# GNSS_GPS.net
KiCad netlist of a schematic drawn in Altium Designer
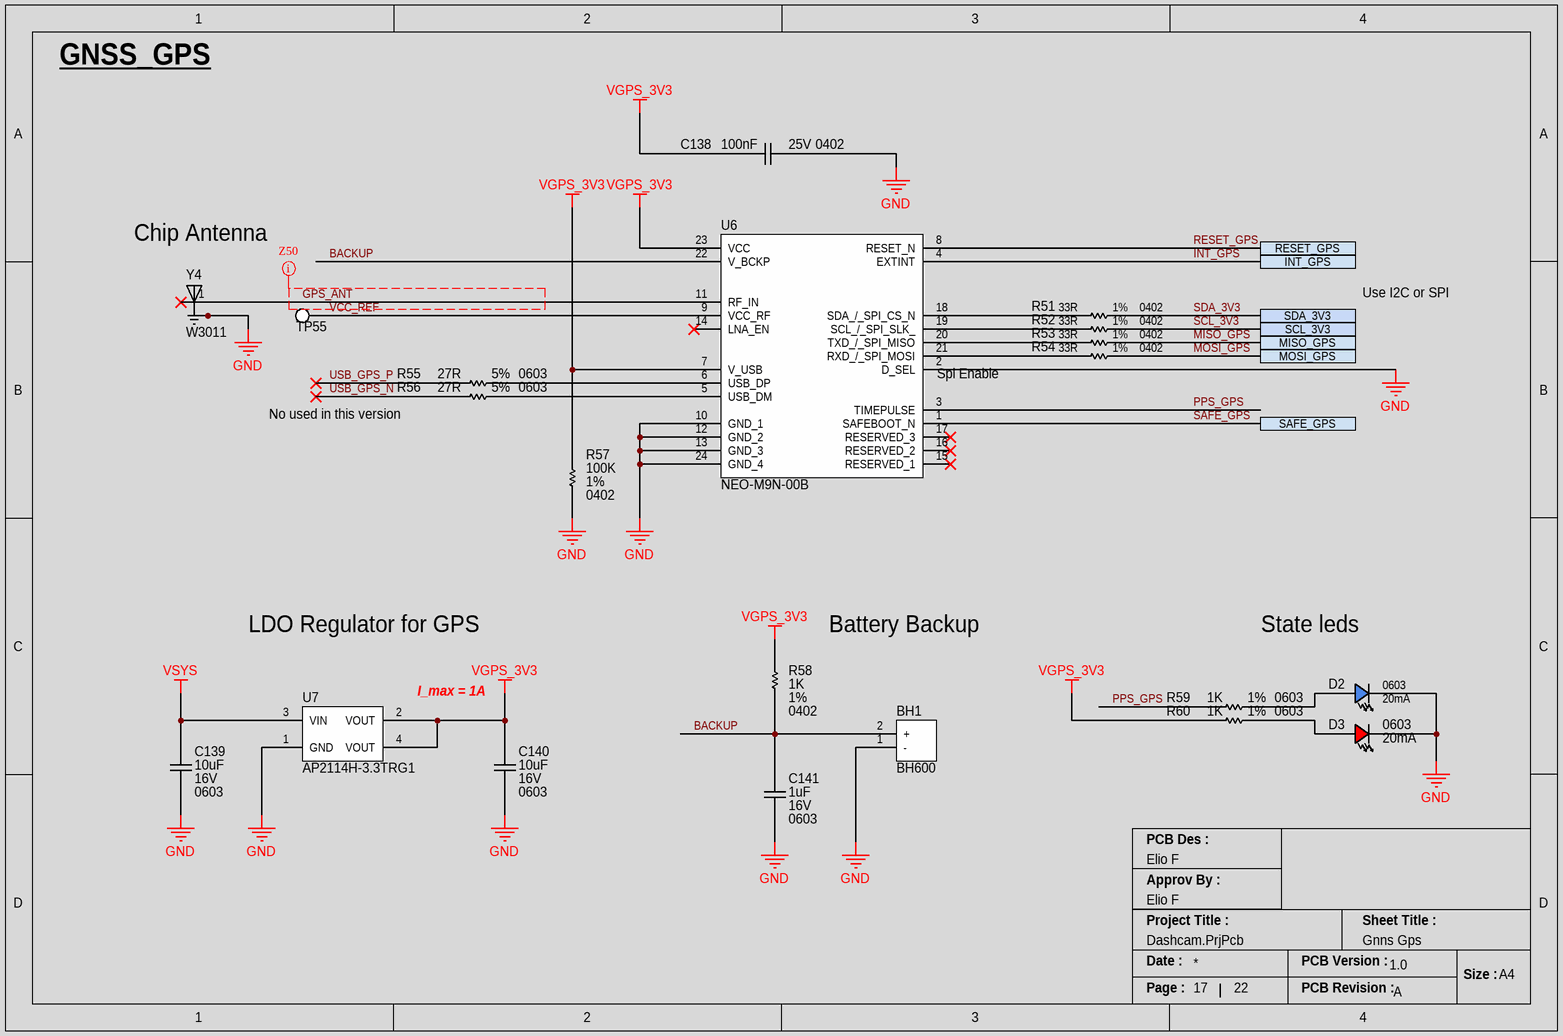
[diagram p0: GNSS_GPS.SchDoc]

(export (version "E")
  (design (tool "Eeschema 10.0.6"))
  (components
    (comp (ref "BH1")
      (value "BH600")
      (footprint "MECH_BATTERY_HOLDER_BH600")
      (description "Battery Holder 1 Cells Thermoplastic Tray")
      (fields (field (name "MANUFACTURER") "Memory Protection Devices"))
      (libsource (lib "Electronic Devices_LIB") (part "MECH_BATTERY_HOLDER_BH600"))
    )
    (comp (ref "C138")
      (value "CC0402KRX5R8BB104")
      (footprint "CAP_0402_CAPC1005X05N")
      (description "Multilayer Ceramic Capacitor, 0.1 uF, 25 V, ± 10%, X7R, 0402 [1005 Metric]")
      (fields
        (field (name "MANUFACTURER") "Yageo")
        (field (name "TOLERANCE") "10%")
        (field (name "CAPACITANCE") "100nF")
        (field (name "VOLTAGE RATING") "25V")
        (field (name "CASE/PACKAGE") "0402")
      )
      (libsource (lib "Electronic Devices_LIB") (part "CAP_100NF_25V_X7R_0402"))
    )
    (comp (ref "C139")
      (value "GRM188R61C106MAALD")
      (footprint "CAP_0603_CAPC1608X08N")
      (description "0603 10 uF 16 V ±20% Tolerance X5R Multilayer Ceramic Chip Capacitor")
      (fields
        (field (name "MANUFACTURER") "Murata")
        (field (name "TOLERANCE") "20%")
        (field (name "VOLTAGE RATING") "16V")
        (field (name "CAPACITANCE") "10uF")
        (field (name "CASE/PACKAGE") "0603")
      )
      (libsource (lib "Electronic Devices_LIB") (part "CAP_10UF_16V_X5R_0603"))
    )
    (comp (ref "C140")
      (value "GRM188R61C106MAALD")
      (footprint "CAP_0603_CAPC1608X08N")
      (description "0603 10 uF 16 V ±20% Tolerance X5R Multilayer Ceramic Chip Capacitor")
      (fields
        (field (name "MANUFACTURER") "Murata")
        (field (name "TOLERANCE") "20%")
        (field (name "VOLTAGE RATING") "16V")
        (field (name "CAPACITANCE") "10uF")
        (field (name "CASE/PACKAGE") "0603")
      )
      (libsource (lib "Electronic Devices_LIB") (part "CAP_10UF_16V_X5R_0603"))
    )
    (comp (ref "C141")
      (value "CL10A105KO8NNNC")
      (footprint "CAP_0603_CAPC1608X08N")
      (description "CAP CER 1UF 16V X5R 0603")
      (fields
        (field (name "MANUFACTURER") "Samsung")
        (field (name "TOLERANCE") "10%")
        (field (name "VOLTAGE RATING") "16V")
        (field (name "CAPACITANCE") "1uF")
        (field (name "CASE/PACKAGE") "0603")
      )
      (libsource (lib "Electronic Devices_LIB") (part "CAP_1UF_16V_X5R_0603"))
    )
    (comp (ref "D2")
      (value "ASCKCB00-NS3T4010302")
      (footprint "LED_0603-BLUE-0.75mm")
      (description "LED Single Chip Blue 467nm 20mA 2-Pin DFN T/R")
      (fields
        (field (name "MANUFACTURER") "Broadcom")
        (field (name "CASE/PACKCAGE") "0603")
        (field (name "TEST CURRENT") "20mA")
      )
      (libsource (lib "Electronic Devices_LIB") (part "LED_DIO_BLUE_20mA_0603_ASCKCB00-NS3T4010302"))
    )
    (comp (ref "D3")
      (value "LTST-C190KRKT")
      (footprint "LED_0603-RED-0.75mm")
      (description "LED,  LTST-C190KRKT")
      (fields
        (field (name "MANUFACTURER") "Vishay Lite-On")
        (field (name "TEST CURRENT") "20mA")
        (field (name "CASE/PACKAGE") "0603")
      )
      (libsource (lib "Electronic Devices_LIB") (part "LED_DIO_RED_20mA_0603"))
    )
    (comp (ref "R51")
      (value "RC0402FR-0733RL")
      (footprint "RES_0402_RESC1005X04N")
      (description "SMD Chip Resistor, 33 Ohm, ± 1%, 62.5 mW, 0402 [1005 Metric], Thick Film, General Purpose")
      (fields
        (field (name "MANUFACTURER") "Yageo")
        (field (name "TOLERANCE") "1%")
        (field (name "RESISTANCE") "33R")
        (field (name "CASE/PACKAGE") "0402")
      )
      (libsource (lib "Electronic Devices_LIB") (part "RES_33R_1%_62.5mW_0402"))
    )
    (comp (ref "R52")
      (value "RC0402FR-0733RL")
      (footprint "RES_0402_RESC1005X04N")
      (description "SMD Chip Resistor, 33 Ohm, ± 1%, 62.5 mW, 0402 [1005 Metric], Thick Film, General Purpose")
      (fields
        (field (name "MANUFACTURER") "Yageo")
        (field (name "TOLERANCE") "1%")
        (field (name "RESISTANCE") "33R")
        (field (name "CASE/PACKAGE") "0402")
      )
      (libsource (lib "Electronic Devices_LIB") (part "RES_33R_1%_62.5mW_0402"))
    )
    (comp (ref "R53")
      (value "RC0402FR-0733RL")
      (footprint "RES_0402_RESC1005X04N")
      (description "SMD Chip Resistor, 33 Ohm, ± 1%, 62.5 mW, 0402 [1005 Metric], Thick Film, General Purpose")
      (fields
        (field (name "MANUFACTURER") "Yageo")
        (field (name "TOLERANCE") "1%")
        (field (name "RESISTANCE") "33R")
        (field (name "CASE/PACKAGE") "0402")
      )
      (libsource (lib "Electronic Devices_LIB") (part "RES_33R_1%_62.5mW_0402"))
    )
    (comp (ref "R54")
      (value "RC0402FR-0733RL")
      (footprint "RES_0402_RESC1005X04N")
      (description "SMD Chip Resistor, 33 Ohm, ± 1%, 62.5 mW, 0402 [1005 Metric], Thick Film, General Purpose")
      (fields
        (field (name "MANUFACTURER") "Yageo")
        (field (name "TOLERANCE") "1%")
        (field (name "RESISTANCE") "33R")
        (field (name "CASE/PACKAGE") "0402")
      )
      (libsource (lib "Electronic Devices_LIB") (part "RES_33R_1%_62.5mW_0402"))
    )
    (comp (ref "R55")
      (value "RC0603JR-0727RL")
      (footprint "RES_0603_RESC1608X04N")
      (description "Res Thick Film 0603 27 Ohm 5% 0.1W(1/10W) ±100ppm/C Pad SMD T/R")
      (fields
        (field (name "MANUFACTURER") "Yageo")
        (field (name "TOLERANCE") "5%")
        (field (name "RESISTANCE") "27R")
        (field (name "CASE/PACKAGE") "0603")
      )
      (libsource (lib "Electronic Devices_LIB") (part "RES_27R_5%_100mW_0603"))
    )
    (comp (ref "R56")
      (value "RC0603JR-0727RL")
      (footprint "RES_0603_RESC1608X04N")
      (description "Res Thick Film 0603 27 Ohm 5% 0.1W(1/10W) ±100ppm/C Pad SMD T/R")
      (fields
        (field (name "MANUFACTURER") "Yageo")
        (field (name "TOLERANCE") "5%")
        (field (name "RESISTANCE") "27R")
        (field (name "CASE/PACKAGE") "0603")
      )
      (libsource (lib "Electronic Devices_LIB") (part "RES_27R_5%_100mW_0603"))
    )
    (comp (ref "R57")
      (value "RC0402FR-07100KL")
      (footprint "RES_0402_RESC1005X04N")
      (description "SMD Chip Resistor, 100 kOhm, ± 1%, 63 mW, 0402 [1005 Metric], Thick Film, General Purpose")
      (fields
        (field (name "MANUFACTURER") "Yageo")
        (field (name "RESISTANCE") "100K")
        (field (name "TOLERANCE") "1%")
        (field (name "CASE/PACKAGE") "0402")
      )
      (libsource (lib "Electronic Devices_LIB") (part "RES_100K_1%_100mW_0402"))
    )
    (comp (ref "R58")
      (value "ERJ-2RKF1001X")
      (footprint "RES_0402_RESC1005X04N")
      (description "RES SMD 1K OHM 1% 1/10W 0402")
      (fields
        (field (name "MANUFACTURER") "Panasonic")
        (field (name "RESISTANCE") "1K")
        (field (name "TOLERANCE") "1%")
        (field (name "CASE/PACKAGE") "0402")
      )
      (libsource (lib "Electronic Devices_LIB") (part "RES_1K_1%_100mW_0402"))
    )
    (comp (ref "R59")
      (value "AC0603FR-101KL")
      (footprint "RES_0603_RESC1608X04N")
      (description "Chip Resistor Automotive Grade Thick Film 0603 1kOhm 1% Paper T/R")
      (fields
        (field (name "MANUFACTURER") "Yageo")
        (field (name "RESISTANCE") "1K")
        (field (name "TOLERANCE") "1%")
        (field (name "CASE/PACKAGE") "0603")
      )
      (libsource (lib "Electronic Devices_LIB") (part "RES_1K_1%_100mW_0603"))
    )
    (comp (ref "R60")
      (value "AC0603FR-101KL")
      (footprint "RES_0603_RESC1608X04N")
      (description "Chip Resistor Automotive Grade Thick Film 0603 1kOhm 1% Paper T/R")
      (fields
        (field (name "MANUFACTURER") "Yageo")
        (field (name "RESISTANCE") "1K")
        (field (name "TOLERANCE") "1%")
        (field (name "CASE/PACKAGE") "0603")
      )
      (libsource (lib "Electronic Devices_LIB") (part "RES_1K_1%_100mW_0603"))
    )
    (comp (ref "TP55")
      (value "NO COMPONENT")
      (footprint "TP_PAD_1.6MM_SMD_ROUND")
      (description "Test Point, SMD pad, round, 1.5mm, 1.6mm, 3mm diameter")
      (libsource (lib "Electronic Devices_LIB") (part "TP_PAD_SMD_Round"))
    )
    (comp (ref "U6")
      (value "NEO-M9N-00B")
      (footprint "IC_MODULE_UBLOX_NEOM9N00B")
      (description "GNSS module, Flash, TCXO, SAW, LNA, LCC, 12x16 mm Professional Grade")
      (fields (field (name "MANUFACTURER") "u-blox"))
      (libsource (lib "Electronic Devices_LIB") (part "IC_MODULE_UBLOX_NEO-M9N-00B"))
    )
    (comp (ref "U7")
      (value "AP2114H-3.3TRG1")
      (footprint "IC_REG_SOT230P700X180-4N")
      (description "IC REG LDO 3.3V 1A SOT223")
      (fields (field (name "MANUFACTURER") "Diodes"))
      (libsource (lib "Electronic Devices_LIB") (part "IC_REG_LDO_3.3V_1A_AP2114H-3.3TRG1"))
    )
    (comp (ref "Y4")
      (value "W3011")
      (footprint "ANTENNA_CHIP_XDCR_W3011")
      (description "Antenna Ceramic 3.4dB Gain 1585.42MHz 2-Pin CSMD")
      (fields (field (name "MANUFACTURER") "Pulse"))
      (libsource (lib "Electronic Devices_LIB") (part "ANT_CHIP_GPS_W3011"))
    )
  )
  (nets
    (net (code "1") (name "/BACKUP") (class "Default")
      (node (ref "BH1") (pin "2") (pinfunction "+_2") (pintype "passive"))
      (node (ref "C141") (pin "2") (pinfunction "2_2") (pintype "passive"))
      (node (ref "R58") (pin "1") (pinfunction "1_1") (pintype "passive"))
      (node (ref "U6") (pin "22") (pinfunction "V_BCKP_22") (pintype "passive"))
    )
    (net (code "2") (name "/GPS_ANT") (class "Default")
      (node (ref "U6") (pin "11") (pinfunction "RF_IN_11") (pintype "passive"))
      (node (ref "Y4") (pin "1") (pinfunction "FEED_1") (pintype "passive"))
    )
    (net (code "3") (name "/INT_GPS") (class "Default")
      (node (ref "U6") (pin "4") (pinfunction "EXTINT_4") (pintype "passive"))
    )
    (net (code "4") (name "/MISO_GPS") (class "Default")
      (node (ref "R53") (pin "2") (pinfunction "2_2") (pintype "passive"))
    )
    (net (code "5") (name "/MOSI_GPS") (class "Default")
      (node (ref "R54") (pin "2") (pinfunction "2_2") (pintype "passive"))
    )
    (net (code "6") (name "/PPS_GPS") (class "Default")
      (node (ref "R59") (pin "1") (pinfunction "1_1") (pintype "passive"))
      (node (ref "U6") (pin "3") (pinfunction "TIMEPULSE_3") (pintype "passive"))
    )
    (net (code "7") (name "/RESET_GPS") (class "Default")
      (node (ref "U6") (pin "8") (pinfunction "RESET_N_8") (pintype "passive"))
    )
    (net (code "8") (name "/SAFE_GPS") (class "Default")
      (node (ref "U6") (pin "1") (pinfunction "SAFEBOOT_N_1") (pintype "passive"))
    )
    (net (code "9") (name "/SCL_3V3") (class "Default")
      (node (ref "R52") (pin "2") (pinfunction "2_2") (pintype "passive"))
    )
    (net (code "10") (name "/SDA_3V3") (class "Default")
      (node (ref "R51") (pin "2") (pinfunction "2_2") (pintype "passive"))
    )
    (net (code "11") (name "/USB_GPS_N") (class "Default")
      (node (ref "R56") (pin "1") (pinfunction "1_1") (pintype "passive+no_connect"))
    )
    (net (code "12") (name "/USB_GPS_P") (class "Default")
      (node (ref "R55") (pin "1") (pinfunction "1_1") (pintype "passive+no_connect"))
    )
    (net (code "13") (name "/VCC_REF") (class "Default")
      (node (ref "TP55") (pin "1") (pinfunction "1_1") (pintype "passive"))
      (node (ref "U6") (pin "9") (pinfunction "VCC_RF_9") (pintype "passive"))
    )
    (net (code "14") (name "GND") (class "Default")
      (node (ref "BH1") (pin "1") (pinfunction "-_1") (pintype "passive"))
      (node (ref "C138") (pin "2") (pinfunction "2_2") (pintype "passive"))
      (node (ref "C139") (pin "1") (pinfunction "1_1") (pintype "passive"))
      (node (ref "C140") (pin "1") (pinfunction "1_1") (pintype "passive"))
      (node (ref "C141") (pin "1") (pinfunction "1_1") (pintype "passive"))
      (node (ref "D2") (pin "1") (pinfunction "C_1") (pintype "passive"))
      (node (ref "D3") (pin "1") (pinfunction "C_1") (pintype "passive"))
      (node (ref "R57") (pin "1") (pinfunction "1_1") (pintype "passive"))
      (node (ref "U6") (pin "10") (pinfunction "GND_1_10") (pintype "passive"))
      (node (ref "U6") (pin "12") (pinfunction "GND_2_12") (pintype "passive"))
      (node (ref "U6") (pin "13") (pinfunction "GND_3_13") (pintype "passive"))
      (node (ref "U6") (pin "2") (pinfunction "D_SEL_2") (pintype "passive"))
      (node (ref "U6") (pin "24") (pinfunction "GND_4_24") (pintype "passive"))
      (node (ref "U7") (pin "1") (pinfunction "GND_1") (pintype "passive"))
      (node (ref "Y4") (pin "2") (pinfunction "GND_2") (pintype "power_in"))
      (node (ref "Y4") (pin "3") (pinfunction "GND_3") (pintype "passive"))
    )
    (net (code "15") (name "Net-(D2-A)") (class "Default")
      (node (ref "D2") (pin "2") (pinfunction "A_2") (pintype "passive"))
      (node (ref "R59") (pin "2") (pinfunction "2_2") (pintype "passive"))
    )
    (net (code "16") (name "Net-(D3-A)") (class "Default")
      (node (ref "D3") (pin "2") (pinfunction "A_2") (pintype "passive"))
      (node (ref "R60") (pin "2") (pinfunction "2_2") (pintype "passive"))
    )
    (net (code "17") (name "Net-(U6-RXD_{slash}_SPI_MOSI)") (class "Default")
      (node (ref "R54") (pin "1") (pinfunction "1_1") (pintype "passive"))
      (node (ref "U6") (pin "21") (pinfunction "RXD_/_SPI_MOSI_21") (pintype "passive"))
    )
    (net (code "18") (name "Net-(U6-SCL_{slash}_SPI_SLK_)") (class "Default")
      (node (ref "R52") (pin "1") (pinfunction "1_1") (pintype "passive"))
      (node (ref "U6") (pin "19") (pinfunction "SCL_/_SPI_SLK__19") (pintype "passive"))
    )
    (net (code "19") (name "Net-(U6-SDA_{slash}_SPI_CS_N)") (class "Default")
      (node (ref "R51") (pin "1") (pinfunction "1_1") (pintype "passive"))
      (node (ref "U6") (pin "18") (pinfunction "SDA_/_SPI_CS_N_18") (pintype "passive"))
    )
    (net (code "20") (name "Net-(U6-TXD_{slash}_SPI_MISO)") (class "Default")
      (node (ref "R53") (pin "1") (pinfunction "1_1") (pintype "passive"))
      (node (ref "U6") (pin "20") (pinfunction "TXD_/_SPI_MISO_20") (pintype "passive"))
    )
    (net (code "21") (name "Net-(U6-USB_DM)") (class "Default")
      (node (ref "R56") (pin "2") (pinfunction "2_2") (pintype "passive"))
      (node (ref "U6") (pin "5") (pinfunction "USB_DM_5") (pintype "passive"))
    )
    (net (code "22") (name "Net-(U6-USB_DP)") (class "Default")
      (node (ref "R55") (pin "2") (pinfunction "2_2") (pintype "passive"))
      (node (ref "U6") (pin "6") (pinfunction "USB_DP_6") (pintype "passive"))
    )
    (net (code "23") (name "VGPS_3V3") (class "Default")
      (node (ref "C138") (pin "1") (pinfunction "1_1") (pintype "passive"))
      (node (ref "C140") (pin "2") (pinfunction "2_2") (pintype "passive"))
      (node (ref "R57") (pin "2") (pinfunction "2_2") (pintype "passive"))
      (node (ref "R58") (pin "2") (pinfunction "2_2") (pintype "passive"))
      (node (ref "R60") (pin "1") (pinfunction "1_1") (pintype "passive"))
      (node (ref "U6") (pin "23") (pinfunction "VCC_23") (pintype "passive"))
      (node (ref "U6") (pin "7") (pinfunction "V_USB_7") (pintype "passive"))
      (node (ref "U7") (pin "2") (pinfunction "VOUT_2") (pintype "passive"))
      (node (ref "U7") (pin "4") (pinfunction "VOUT_4") (pintype "passive"))
    )
    (net (code "24") (name "VSYS") (class "Default")
      (node (ref "C139") (pin "2") (pinfunction "2_2") (pintype "passive"))
      (node (ref "U7") (pin "3") (pinfunction "VIN_3") (pintype "passive"))
    )
    (net (code "25") (name "unconnected-(U6-LNA_EN-Pad14)") (class "Default")
      (node (ref "U6") (pin "14") (pinfunction "LNA_EN_14") (pintype "passive+no_connect"))
    )
    (net (code "26") (name "unconnected-(U6-RESERVED_1-Pad15)") (class "Default")
      (node (ref "U6") (pin "15") (pinfunction "RESERVED_1_15") (pintype "passive+no_connect"))
    )
    (net (code "27") (name "unconnected-(U6-RESERVED_2-Pad16)") (class "Default")
      (node (ref "U6") (pin "16") (pinfunction "RESERVED_2_16") (pintype "passive+no_connect"))
    )
    (net (code "28") (name "unconnected-(U6-RESERVED_3-Pad17)") (class "Default")
      (node (ref "U6") (pin "17") (pinfunction "RESERVED_3_17") (pintype "passive+no_connect"))
    )
    (net (code "29") (name "unconnected-(Y4-NC-Pad2)") (class "Default")
      (node (ref "Y4") (pin "2") (pinfunction "NC_2") (pintype "passive+no_connect"))
    )
  )
)
